# dual_encoder_i2c_shield_revA.net
KiCad netlist of a schematic drawn in EAGLE
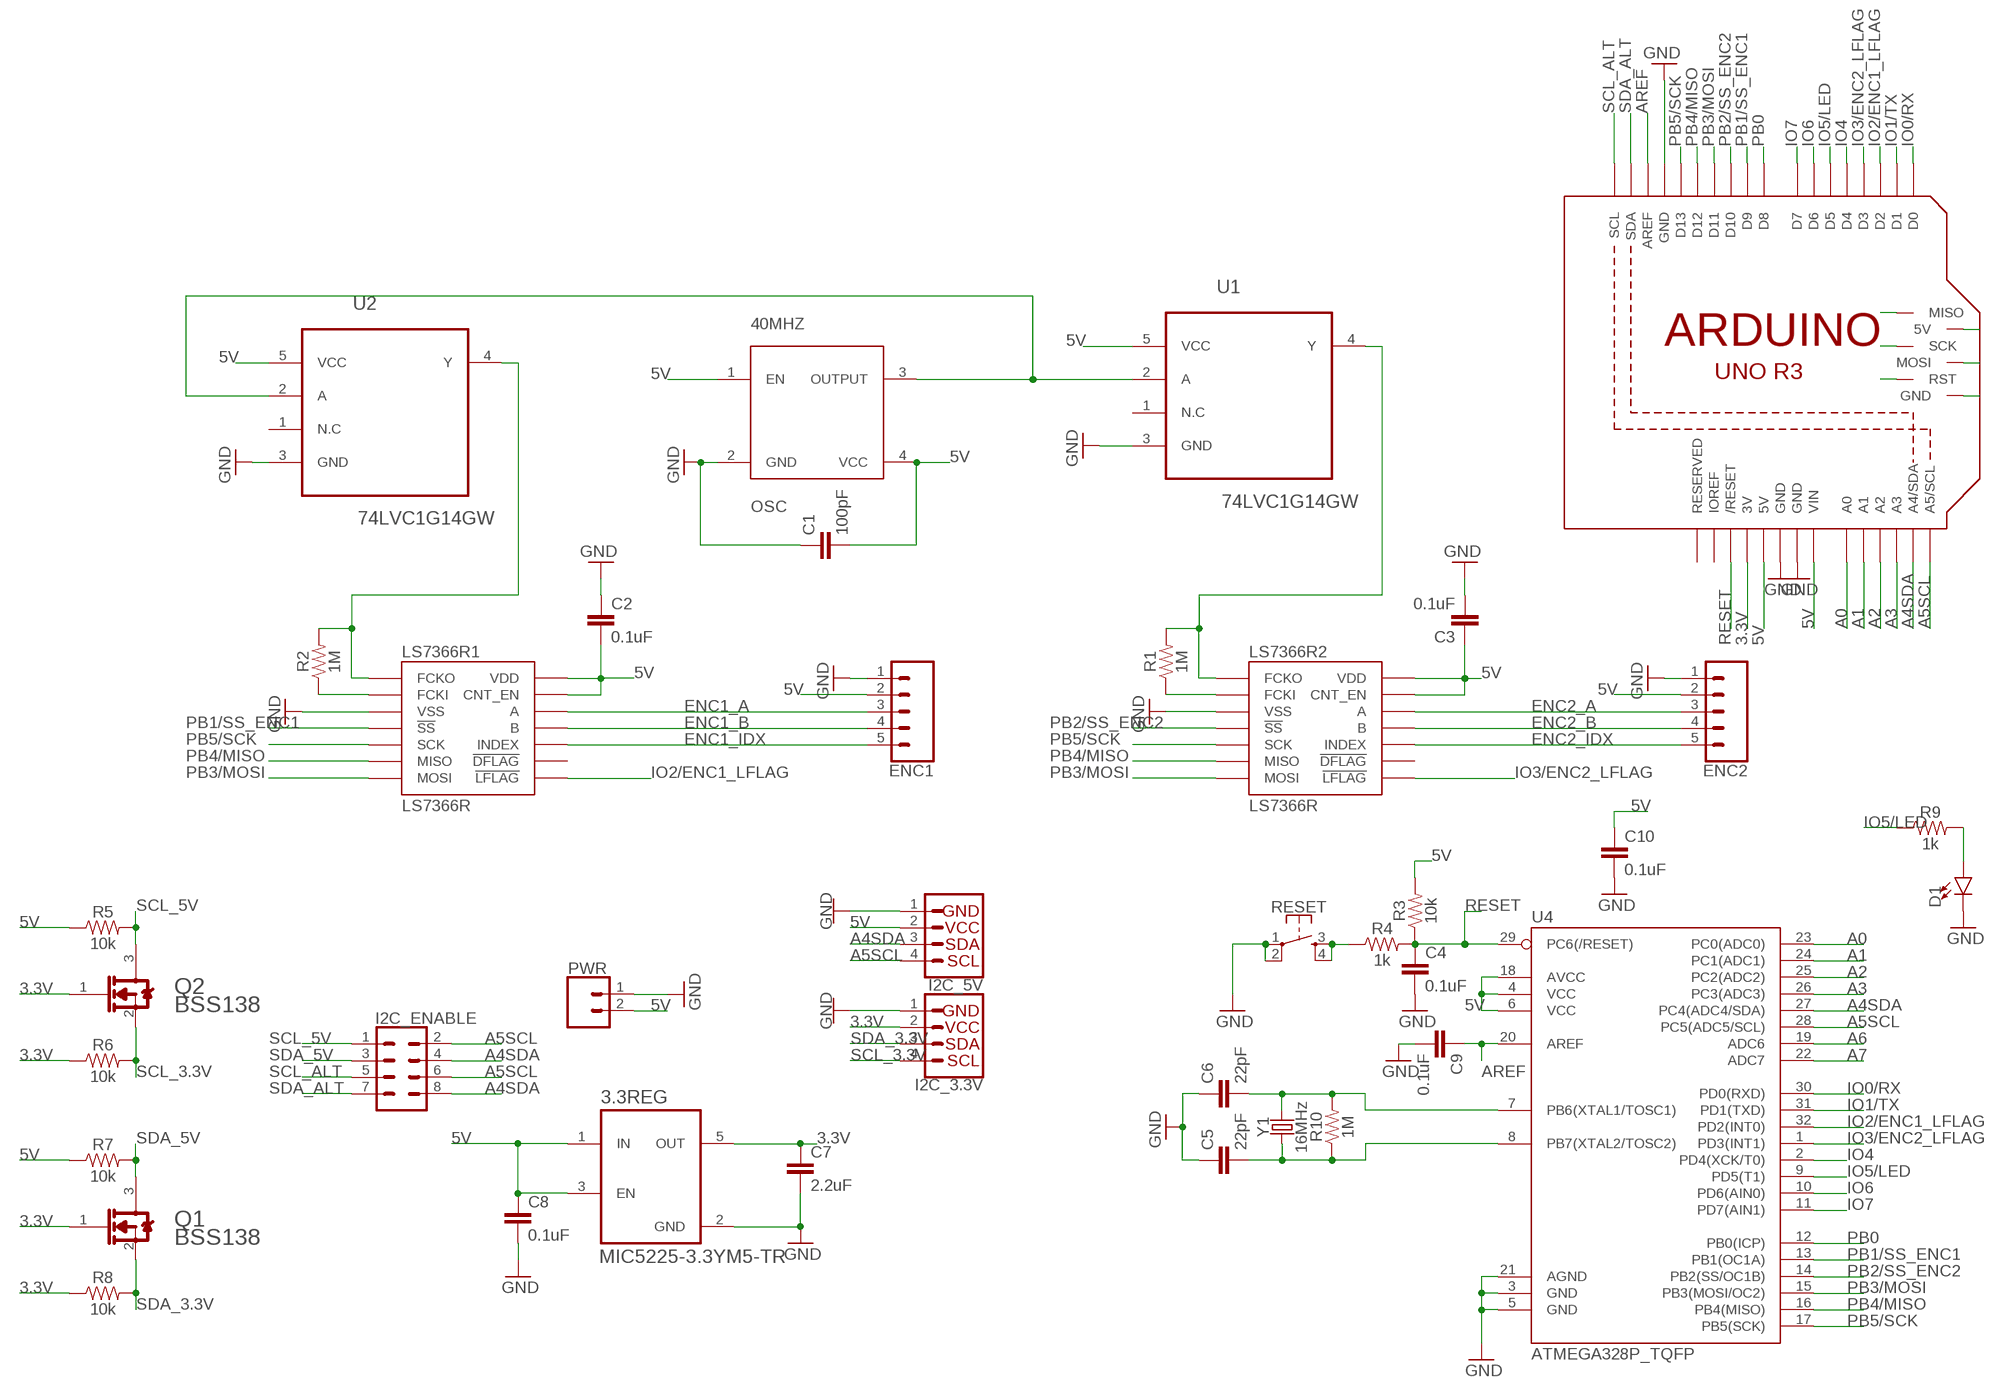
[diagram p0: schematic, sheet 1]

(export (version "E")
  (design (tool "Eeschema 10.0.6"))
  (components
    (comp (ref "3.3REG")
      (value "MIC5225-3.3YM5-TR")
      (footprint "eagle-import:SOT95P280X145-5N")
      (fields (field (name "MF") "Microchip"))
      (libsource (lib "eagle-import") (part "MIC5225-3.3YM5-TR"))
    )
    (comp (ref "40MHZ")
      (value "OSC")
      (footprint "eagle-import:CB3OSCILLATOR")
      (libsource (lib "eagle-import") (part "OSC"))
    )
    (comp (ref "C1")
      (value "100pF")
      (footprint "eagle-import:0603")
      (libsource (lib "eagle-import") (part "100PF-0603-50V-5%"))
    )
    (comp (ref "C2")
      (value "0.1uF")
      (footprint "eagle-import:0603")
      (libsource (lib "eagle-import") (part "0.1UF-0603-25V-5%"))
    )
    (comp (ref "C3")
      (value "0.1uF")
      (footprint "eagle-import:0603")
      (libsource (lib "eagle-import") (part "0.1UF-0603-25V-5%"))
    )
    (comp (ref "C4")
      (value "0.1uF")
      (footprint "eagle-import:0603")
      (libsource (lib "eagle-import") (part "0.1UF-0603-25V-5%"))
    )
    (comp (ref "C5")
      (value "22pF")
      (footprint "eagle-import:0603")
      (libsource (lib "eagle-import") (part "22PF-0603-50V-5%"))
    )
    (comp (ref "C6")
      (value "22pF")
      (footprint "eagle-import:0603")
      (libsource (lib "eagle-import") (part "22PF-0603-50V-5%"))
    )
    (comp (ref "C7")
      (value "2.2uF")
      (footprint "eagle-import:0603")
      (libsource (lib "eagle-import") (part "2.2UF-0603-10V-20%"))
    )
    (comp (ref "C8")
      (value "0.1uF")
      (footprint "eagle-import:0603")
      (libsource (lib "eagle-import") (part "0.1UF-0603-25V-5%"))
    )
    (comp (ref "C9")
      (value "0.1uF")
      (footprint "eagle-import:0603")
      (libsource (lib "eagle-import") (part "0.1UF-0603-25V-5%"))
    )
    (comp (ref "C10")
      (value "0.1uF")
      (footprint "eagle-import:0603")
      (libsource (lib "eagle-import") (part "0.1UF-0603-25V-5%"))
    )
    (comp (ref "D1")
      (value "LED0603")
      (footprint "eagle-import:LED-0603")
      (libsource (lib "eagle-import") (part "LED0603"))
    )
    (comp (ref "ENC1")
      (value "CONN_05")
      (footprint "eagle-import:1X05")
      (libsource (lib "eagle-import") (part "CONN_05"))
    )
    (comp (ref "ENC2")
      (value "CONN_05")
      (footprint "eagle-import:1X05")
      (libsource (lib "eagle-import") (part "CONN_05"))
    )
    (comp (ref "I2C_3.3V")
      (value "QWIIC_CONNECTORJS-1MM")
      (footprint "eagle-import:JST04_1MM_RA")
      (libsource (lib "eagle-import") (part "QWIIC_CONNECTORJS-1MM"))
    )
    (comp (ref "I2C_5V")
      (value "QWIIC_CONNECTORJS-1MM")
      (footprint "eagle-import:JST04_1MM_RA")
      (libsource (lib "eagle-import") (part "QWIIC_CONNECTORJS-1MM"))
    )
    (comp (ref "I2C_ENABLE")
      (value "CONN_04X2")
      (footprint "eagle-import:2X4")
      (libsource (lib "eagle-import") (part "CONN_04X2"))
    )
    (comp (ref "LS7366R1")
      (value "LS7366R")
      (footprint "eagle-import:SOIC14")
      (fields (field (name "MF") "LSI"))
      (libsource (lib "eagle-import") (part "LS7366R"))
    )
    (comp (ref "LS7366R2")
      (value "LS7366R")
      (footprint "eagle-import:SOIC14")
      (fields (field (name "MF") "LSI"))
      (libsource (lib "eagle-import") (part "LS7366R"))
    )
    (comp (ref "M1")
      (value "ARDUINO_R3_ICSP")
      (footprint "eagle-import:ARDUINOR3_ICSP")
      (libsource (lib "eagle-import") (part "ARDUINO_R3_ICSP"))
    )
    (comp (ref "PWR")
      (value "CONN_02-JST-2MM-SMT")
      (footprint "eagle-import:JST-2-SMD")
      (libsource (lib "eagle-import") (part "CONN_02-JST-2MM-SMT"))
    )
    (comp (ref "Q1")
      (value "ON_SEMI_BSS138ON_SEMI_BSS138_0_0")
      (footprint "eagle-import:ON_SEMI_BSS138_0")
      (fields
        (field (name "DIGIKEY_PART_NUMBER") "BSS138CT-ND")
        (field (name "MF") "ON Semi")
        (field (name "MOUSER_PART_NUMBER") "512-BSS138")
      )
      (libsource (lib "eagle-import") (part "ON_SEMI_BSS138ON_SEMI_BSS138_0_0"))
    )
    (comp (ref "Q2")
      (value "ON_SEMI_BSS138ON_SEMI_BSS138_0_0")
      (footprint "eagle-import:ON_SEMI_BSS138_0")
      (fields
        (field (name "DIGIKEY_PART_NUMBER") "BSS138CT-ND")
        (field (name "MF") "ON Semi")
        (field (name "MOUSER_PART_NUMBER") "512-BSS138")
      )
      (libsource (lib "eagle-import") (part "ON_SEMI_BSS138ON_SEMI_BSS138_0_0"))
    )
    (comp (ref "R1")
      (value "1M")
      (footprint "eagle-import:0603")
      (libsource (lib "eagle-import") (part "1MOHM-0603-1/4W-5%"))
    )
    (comp (ref "R2")
      (value "1M")
      (footprint "eagle-import:0603")
      (libsource (lib "eagle-import") (part "1MOHM-0603-1/4W-5%"))
    )
    (comp (ref "R3")
      (value "10k")
      (footprint "eagle-import:0603")
      (libsource (lib "eagle-import") (part "10KOHM-0603-1/10W-1%"))
    )
    (comp (ref "R4")
      (value "1k")
      (footprint "eagle-import:0603")
      (libsource (lib "eagle-import") (part "1KOHM-0603-1/10W-1%"))
    )
    (comp (ref "R5")
      (value "10k")
      (footprint "eagle-import:0603")
      (libsource (lib "eagle-import") (part "10KOHM-0603-1/10W-1%"))
    )
    (comp (ref "R6")
      (value "10k")
      (footprint "eagle-import:0603")
      (libsource (lib "eagle-import") (part "10KOHM-0603-1/10W-1%"))
    )
    (comp (ref "R7")
      (value "10k")
      (footprint "eagle-import:0603")
      (libsource (lib "eagle-import") (part "10KOHM-0603-1/10W-1%"))
    )
    (comp (ref "R8")
      (value "10k")
      (footprint "eagle-import:0603")
      (libsource (lib "eagle-import") (part "10KOHM-0603-1/10W-1%"))
    )
    (comp (ref "R9")
      (value "1k")
      (footprint "eagle-import:0603")
      (libsource (lib "eagle-import") (part "1KOHM-0603-1/10W-1%"))
    )
    (comp (ref "R10")
      (value "1M")
      (footprint "eagle-import:0603")
      (libsource (lib "eagle-import") (part "1MOHM-0603-1/4W-5%"))
    )
    (comp (ref "RESET")
      (value "MOMENTARY-SWITCH-SPST-2-SMD-5.2MM")
      (footprint "eagle-import:TACTILE_SWITCH_SMD_5.2MM")
      (libsource (lib "eagle-import") (part "MOMENTARY-SWITCH-SPST-2-SMD-5.2MM"))
    )
    (comp (ref "U1")
      (value "74LVC1G14GW")
      (footprint "eagle-import:SOT65P210X110-5N")
      (fields (field (name "MF") "NXP Semiconductors"))
      (libsource (lib "eagle-import") (part "74LVC1G14GW"))
    )
    (comp (ref "U2")
      (value "74LVC1G14GW")
      (footprint "eagle-import:SOT65P210X110-5N")
      (fields (field (name "MF") "NXP Semiconductors"))
      (libsource (lib "eagle-import") (part "74LVC1G14GW"))
    )
    (comp (ref "U4")
      (value "ATMEGA328P_TQFP")
      (footprint "eagle-import:TQFP32-08")
      (libsource (lib "eagle-import") (part "ATMEGA328P_TQFP"))
    )
    (comp (ref "Y1")
      (value "16MHz")
      (footprint "eagle-import:HC49US")
      (libsource (lib "eagle-import") (part "CRYSTAL-16MHZPTH-HC49US"))
    )
  )
  (nets
    (net (code "1") (name "/3.3V") (class "Default")
      (node (ref "3.3REG") (pin "5") (pinfunction "OUT_5") (pintype "output"))
      (node (ref "C7") (pin "1") (pinfunction "1_1") (pintype "passive"))
      (node (ref "I2C_3.3V") (pin "2") (pinfunction "2_2") (pintype "power_in"))
      (node (ref "M1") (pin "3V") (pinfunction "3V_3V") (pintype "power_in"))
      (node (ref "Q1") (pin "1") (pinfunction "G_1") (pintype "bidirectional"))
      (node (ref "Q2") (pin "1") (pinfunction "G_1") (pintype "bidirectional"))
      (node (ref "R6") (pin "1") (pinfunction "1_1") (pintype "passive"))
      (node (ref "R8") (pin "1") (pinfunction "1_1") (pintype "passive"))
    )
    (net (code "2") (name "/5V") (class "Default")
      (node (ref "3.3REG") (pin "1") (pinfunction "IN_1") (pintype "input"))
      (node (ref "3.3REG") (pin "3") (pinfunction "EN_3") (pintype "input"))
      (node (ref "40MHZ") (pin "1") (pinfunction "EN_1") (pintype "input"))
      (node (ref "40MHZ") (pin "4") (pinfunction "VCC_4") (pintype "input"))
      (node (ref "C1") (pin "2") (pinfunction "2_2") (pintype "passive"))
      (node (ref "C10") (pin "1") (pinfunction "1_1") (pintype "passive"))
      (node (ref "C2") (pin "2") (pinfunction "2_2") (pintype "passive"))
      (node (ref "C3") (pin "1") (pinfunction "1_1") (pintype "passive"))
      (node (ref "C8") (pin "1") (pinfunction "1_1") (pintype "passive"))
      (node (ref "ENC1") (pin "2") (pinfunction "2_2") (pintype "passive"))
      (node (ref "ENC2") (pin "2") (pinfunction "2_2") (pintype "passive"))
      (node (ref "I2C_5V") (pin "2") (pinfunction "2_2") (pintype "power_in"))
      (node (ref "LS7366R1") (pin "13") (pinfunction "CNT_EN_13") (pintype "bidirectional"))
      (node (ref "LS7366R1") (pin "14") (pinfunction "VDD_14") (pintype "bidirectional"))
      (node (ref "LS7366R2") (pin "13") (pinfunction "CNT_EN_13") (pintype "bidirectional"))
      (node (ref "LS7366R2") (pin "14") (pinfunction "VDD_14") (pintype "bidirectional"))
      (node (ref "M1") (pin "5V") (pinfunction "5V_5V") (pintype "power_in"))
      (node (ref "M1") (pin "5V_ICSP") (pinfunction "5V_5V_ICSP") (pintype "passive"))
      (node (ref "M1") (pin "VIN") (pinfunction "VIN_VIN") (pintype "power_in"))
      (node (ref "PWR") (pin "2") (pinfunction "1_2") (pintype "passive"))
      (node (ref "R3") (pin "2") (pinfunction "2_2") (pintype "passive"))
      (node (ref "R5") (pin "1") (pinfunction "1_1") (pintype "passive"))
      (node (ref "R7") (pin "1") (pinfunction "1_1") (pintype "passive"))
      (node (ref "U1") (pin "5") (pinfunction "VCC_5") (pintype "power_in"))
      (node (ref "U2") (pin "5") (pinfunction "VCC_5") (pintype "power_in"))
      (node (ref "U4") (pin "18") (pinfunction "AVCC_18") (pintype "bidirectional"))
      (node (ref "U4") (pin "4") (pinfunction "VCC_4") (pintype "bidirectional"))
      (node (ref "U4") (pin "6") (pinfunction "VCC_6") (pintype "bidirectional"))
    )
    (net (code "3") (name "/A0") (class "Default")
      (node (ref "M1") (pin "A0") (pinfunction "A0_A0") (pintype "bidirectional"))
      (node (ref "U4") (pin "23") (pinfunction "PC0(ADC0)_23") (pintype "bidirectional"))
    )
    (net (code "4") (name "/A1") (class "Default")
      (node (ref "M1") (pin "A1") (pinfunction "A1_A1") (pintype "bidirectional"))
      (node (ref "U4") (pin "24") (pinfunction "PC1(ADC1)_24") (pintype "bidirectional"))
    )
    (net (code "5") (name "/A2") (class "Default")
      (node (ref "M1") (pin "A2") (pinfunction "A2_A2") (pintype "bidirectional"))
      (node (ref "U4") (pin "25") (pinfunction "PC2(ADC2)_25") (pintype "bidirectional"))
    )
    (net (code "6") (name "/A3") (class "Default")
      (node (ref "M1") (pin "A3") (pinfunction "A3_A3") (pintype "bidirectional"))
      (node (ref "U4") (pin "26") (pinfunction "PC3(ADC3)_26") (pintype "bidirectional"))
    )
    (net (code "7") (name "/A4SDA") (class "Default")
      (node (ref "I2C_5V") (pin "3") (pinfunction "3_3") (pintype "passive"))
      (node (ref "I2C_ENABLE") (pin "4") (pinfunction "4_4") (pintype "passive"))
      (node (ref "I2C_ENABLE") (pin "8") (pinfunction "8_8") (pintype "passive"))
      (node (ref "M1") (pin "A4") (pinfunction "A4/SDA_A4") (pintype "bidirectional"))
      (node (ref "U4") (pin "27") (pinfunction "PC4(ADC4/SDA)_27") (pintype "bidirectional"))
    )
    (net (code "8") (name "/A5SCL") (class "Default")
      (node (ref "I2C_5V") (pin "4") (pinfunction "4_4") (pintype "passive"))
      (node (ref "I2C_ENABLE") (pin "2") (pinfunction "2_2") (pintype "passive"))
      (node (ref "I2C_ENABLE") (pin "6") (pinfunction "6_6") (pintype "passive"))
      (node (ref "M1") (pin "A5") (pinfunction "A5/SCL_A5") (pintype "bidirectional"))
      (node (ref "U4") (pin "28") (pinfunction "PC5(ADC5/SCL)_28") (pintype "bidirectional"))
    )
    (net (code "9") (name "/A6") (class "Default")
      (node (ref "U4") (pin "19") (pinfunction "ADC6_19") (pintype "bidirectional"))
    )
    (net (code "10") (name "/A7") (class "Default")
      (node (ref "U4") (pin "22") (pinfunction "ADC7_22") (pintype "bidirectional"))
    )
    (net (code "11") (name "/AREF") (class "Default")
      (node (ref "C9") (pin "1") (pinfunction "1_1") (pintype "passive"))
      (node (ref "M1") (pin "AREF") (pinfunction "AREF_AREF") (pintype "bidirectional"))
      (node (ref "U4") (pin "20") (pinfunction "AREF_20") (pintype "bidirectional"))
    )
    (net (code "12") (name "/ENC1_A") (class "Default")
      (node (ref "ENC1") (pin "3") (pinfunction "3_3") (pintype "passive"))
      (node (ref "LS7366R1") (pin "12") (pinfunction "A_12") (pintype "bidirectional"))
    )
    (net (code "13") (name "/ENC1_B") (class "Default")
      (node (ref "ENC1") (pin "4") (pinfunction "4_4") (pintype "passive"))
      (node (ref "LS7366R1") (pin "11") (pinfunction "B_11") (pintype "bidirectional"))
    )
    (net (code "14") (name "/ENC1_IDX") (class "Default")
      (node (ref "ENC1") (pin "5") (pinfunction "5_5") (pintype "passive"))
      (node (ref "LS7366R1") (pin "10") (pinfunction "INDEX_10") (pintype "bidirectional"))
    )
    (net (code "15") (name "/ENC2_A") (class "Default")
      (node (ref "ENC2") (pin "3") (pinfunction "3_3") (pintype "passive"))
      (node (ref "LS7366R2") (pin "12") (pinfunction "A_12") (pintype "bidirectional"))
    )
    (net (code "16") (name "/ENC2_B") (class "Default")
      (node (ref "ENC2") (pin "4") (pinfunction "4_4") (pintype "passive"))
      (node (ref "LS7366R2") (pin "11") (pinfunction "B_11") (pintype "bidirectional"))
    )
    (net (code "17") (name "/ENC2_IDX") (class "Default")
      (node (ref "ENC2") (pin "5") (pinfunction "5_5") (pintype "passive"))
      (node (ref "LS7366R2") (pin "10") (pinfunction "INDEX_10") (pintype "bidirectional"))
    )
    (net (code "18") (name "/IO0{slash}RX") (class "Default")
      (node (ref "M1") (pin "D0") (pinfunction "D0_D0") (pintype "bidirectional"))
      (node (ref "U4") (pin "30") (pinfunction "PD0(RXD)_30") (pintype "bidirectional"))
    )
    (net (code "19") (name "/IO1{slash}TX") (class "Default")
      (node (ref "M1") (pin "D1") (pinfunction "D1_D1") (pintype "bidirectional"))
      (node (ref "U4") (pin "31") (pinfunction "PD1(TXD)_31") (pintype "bidirectional"))
    )
    (net (code "20") (name "/IO2{slash}ENC1_LFLAG") (class "Default")
      (node (ref "LS7366R1") (pin "8") (pinfunction "~{LFLAG}_8") (pintype "bidirectional"))
      (node (ref "M1") (pin "D2") (pinfunction "D2_D2") (pintype "bidirectional"))
      (node (ref "U4") (pin "32") (pinfunction "PD2(INT0)_32") (pintype "bidirectional"))
    )
    (net (code "21") (name "/IO3{slash}ENC2_LFLAG") (class "Default")
      (node (ref "LS7366R2") (pin "8") (pinfunction "~{LFLAG}_8") (pintype "bidirectional"))
      (node (ref "M1") (pin "D3") (pinfunction "D3_D3") (pintype "bidirectional"))
      (node (ref "U4") (pin "1") (pinfunction "PD3(INT1)_1") (pintype "bidirectional"))
    )
    (net (code "22") (name "/IO4") (class "Default")
      (node (ref "M1") (pin "D4") (pinfunction "D4_D4") (pintype "bidirectional"))
      (node (ref "U4") (pin "2") (pinfunction "PD4(XCK/T0)_2") (pintype "bidirectional"))
    )
    (net (code "23") (name "/IO5{slash}LED") (class "Default")
      (node (ref "M1") (pin "D5") (pinfunction "D5_D5") (pintype "bidirectional"))
      (node (ref "R9") (pin "1") (pinfunction "1_1") (pintype "passive"))
      (node (ref "U4") (pin "9") (pinfunction "PD5(T1)_9") (pintype "bidirectional"))
    )
    (net (code "24") (name "/IO6") (class "Default")
      (node (ref "M1") (pin "D6") (pinfunction "D6_D6") (pintype "bidirectional"))
      (node (ref "U4") (pin "10") (pinfunction "PD6(AIN0)_10") (pintype "bidirectional"))
    )
    (net (code "25") (name "/IO7") (class "Default")
      (node (ref "M1") (pin "D7") (pinfunction "D7_D7") (pintype "bidirectional"))
      (node (ref "U4") (pin "11") (pinfunction "PD7(AIN1)_11") (pintype "bidirectional"))
    )
    (net (code "26") (name "/PB0") (class "Default")
      (node (ref "M1") (pin "D8") (pinfunction "D8_D8") (pintype "bidirectional"))
      (node (ref "U4") (pin "12") (pinfunction "PB0(ICP)_12") (pintype "bidirectional"))
    )
    (net (code "27") (name "/PB1{slash}SS_ENC1") (class "Default")
      (node (ref "LS7366R1") (pin "4") (pinfunction "~{SS}_4") (pintype "bidirectional"))
      (node (ref "M1") (pin "D9") (pinfunction "D9_D9") (pintype "bidirectional"))
      (node (ref "U4") (pin "13") (pinfunction "PB1(OC1A)_13") (pintype "bidirectional"))
    )
    (net (code "28") (name "/PB2{slash}SS_ENC2") (class "Default")
      (node (ref "LS7366R2") (pin "4") (pinfunction "~{SS}_4") (pintype "bidirectional"))
      (node (ref "M1") (pin "D10") (pinfunction "D10_D10") (pintype "bidirectional"))
      (node (ref "U4") (pin "14") (pinfunction "PB2(SS/OC1B)_14") (pintype "bidirectional"))
    )
    (net (code "29") (name "/PB3{slash}MOSI") (class "Default")
      (node (ref "LS7366R1") (pin "7") (pinfunction "MOSI_7") (pintype "bidirectional"))
      (node (ref "LS7366R2") (pin "7") (pinfunction "MOSI_7") (pintype "bidirectional"))
      (node (ref "M1") (pin "D11") (pinfunction "D11_D11") (pintype "bidirectional"))
      (node (ref "M1") (pin "MOSI") (pinfunction "MOSI_MOSI") (pintype "passive"))
      (node (ref "U4") (pin "15") (pinfunction "PB3(MOSI/OC2)_15") (pintype "bidirectional"))
    )
    (net (code "30") (name "/PB4{slash}MISO") (class "Default")
      (node (ref "LS7366R1") (pin "6") (pinfunction "MISO_6") (pintype "bidirectional"))
      (node (ref "LS7366R2") (pin "6") (pinfunction "MISO_6") (pintype "bidirectional"))
      (node (ref "M1") (pin "D12") (pinfunction "D12_D12") (pintype "bidirectional"))
      (node (ref "M1") (pin "MISO") (pinfunction "MISO_MISO") (pintype "passive"))
      (node (ref "U4") (pin "16") (pinfunction "PB4(MISO)_16") (pintype "bidirectional"))
    )
    (net (code "31") (name "/PB5{slash}SCK") (class "Default")
      (node (ref "LS7366R1") (pin "5") (pinfunction "SCK_5") (pintype "bidirectional"))
      (node (ref "LS7366R2") (pin "5") (pinfunction "SCK_5") (pintype "bidirectional"))
      (node (ref "M1") (pin "D13") (pinfunction "D13_D13") (pintype "bidirectional"))
      (node (ref "M1") (pin "SCK") (pinfunction "SCK_SCK") (pintype "passive"))
      (node (ref "U4") (pin "17") (pinfunction "PB5(SCK)_17") (pintype "bidirectional"))
    )
    (net (code "32") (name "/RESET") (class "Default")
      (node (ref "C4") (pin "1") (pinfunction "1_1") (pintype "passive"))
      (node (ref "M1") (pin "RESET") (pinfunction "/RESET_RESET") (pintype "bidirectional"))
      (node (ref "M1") (pin "RESET_ICSP") (pinfunction "RST_RESET_ICSP") (pintype "passive"))
      (node (ref "R3") (pin "1") (pinfunction "1_1") (pintype "passive"))
      (node (ref "R4") (pin "2") (pinfunction "2_2") (pintype "passive"))
      (node (ref "U4") (pin "29") (pinfunction "PC6(/RESET)_29") (pintype "bidirectional"))
    )
    (net (code "33") (name "/SCL_3.3V") (class "Default")
      (node (ref "I2C_3.3V") (pin "4") (pinfunction "4_4") (pintype "passive"))
      (node (ref "Q2") (pin "2") (pinfunction "S_2") (pintype "bidirectional"))
      (node (ref "R6") (pin "2") (pinfunction "2_2") (pintype "passive"))
    )
    (net (code "34") (name "/SCL_5V") (class "Default")
      (node (ref "I2C_ENABLE") (pin "1") (pinfunction "1_1") (pintype "passive"))
      (node (ref "Q2") (pin "3") (pinfunction "D_3") (pintype "bidirectional"))
      (node (ref "R5") (pin "2") (pinfunction "2_2") (pintype "passive"))
    )
    (net (code "35") (name "/SCL_ALT") (class "Default")
      (node (ref "I2C_ENABLE") (pin "5") (pinfunction "5_5") (pintype "passive"))
      (node (ref "M1") (pin "SCL") (pinfunction "SCL_SCL") (pintype "bidirectional"))
    )
    (net (code "36") (name "/SDA_3.3V") (class "Default")
      (node (ref "I2C_3.3V") (pin "3") (pinfunction "3_3") (pintype "passive"))
      (node (ref "Q1") (pin "2") (pinfunction "S_2") (pintype "bidirectional"))
      (node (ref "R8") (pin "2") (pinfunction "2_2") (pintype "passive"))
    )
    (net (code "37") (name "/SDA_5V") (class "Default")
      (node (ref "I2C_ENABLE") (pin "3") (pinfunction "3_3") (pintype "passive"))
      (node (ref "Q1") (pin "3") (pinfunction "D_3") (pintype "bidirectional"))
      (node (ref "R7") (pin "2") (pinfunction "2_2") (pintype "passive"))
    )
    (net (code "38") (name "/SDA_ALT") (class "Default")
      (node (ref "I2C_ENABLE") (pin "7") (pinfunction "7_7") (pintype "passive"))
      (node (ref "M1") (pin "SDA") (pinfunction "SDA_SDA") (pintype "bidirectional"))
    )
    (net (code "39") (name "GND") (class "Default")
      (node (ref "3.3REG") (pin "2") (pinfunction "GND_2") (pintype "power_in"))
      (node (ref "40MHZ") (pin "2") (pinfunction "GND_2") (pintype "input"))
      (node (ref "C1") (pin "1") (pinfunction "1_1") (pintype "passive"))
      (node (ref "C10") (pin "2") (pinfunction "2_2") (pintype "passive"))
      (node (ref "C2") (pin "1") (pinfunction "1_1") (pintype "passive"))
      (node (ref "C3") (pin "2") (pinfunction "2_2") (pintype "passive"))
      (node (ref "C4") (pin "2") (pinfunction "2_2") (pintype "passive"))
      (node (ref "C5") (pin "1") (pinfunction "1_1") (pintype "passive"))
      (node (ref "C6") (pin "1") (pinfunction "1_1") (pintype "passive"))
      (node (ref "C7") (pin "2") (pinfunction "2_2") (pintype "passive"))
      (node (ref "C8") (pin "2") (pinfunction "2_2") (pintype "passive"))
      (node (ref "C9") (pin "2") (pinfunction "2_2") (pintype "passive"))
      (node (ref "D1") (pin "C") (pinfunction "C_C") (pintype "passive"))
      (node (ref "ENC1") (pin "1") (pinfunction "1_1") (pintype "passive"))
      (node (ref "ENC2") (pin "1") (pinfunction "1_1") (pintype "passive"))
      (node (ref "I2C_3.3V") (pin "1") (pinfunction "1_1") (pintype "power_in"))
      (node (ref "I2C_5V") (pin "1") (pinfunction "1_1") (pintype "power_in"))
      (node (ref "LS7366R1") (pin "3") (pinfunction "VSS_3") (pintype "bidirectional"))
      (node (ref "LS7366R2") (pin "3") (pinfunction "VSS_3") (pintype "bidirectional"))
      (node (ref "M1") (pin "GND") (pinfunction "GND_GND") (pintype "power_in"))
      (node (ref "M1") (pin "GND@1") (pinfunction "GND_GND@1") (pintype "power_in"))
      (node (ref "M1") (pin "GND@2") (pinfunction "GND_GND@2") (pintype "passive"))
      (node (ref "M1") (pin "GND@3") (pinfunction "GND_GND@3") (pintype "power_in"))
      (node (ref "PWR") (pin "1") (pinfunction "2_1") (pintype "passive"))
      (node (ref "RESET") (pin "1") (pinfunction "1_1") (pintype "passive"))
      (node (ref "RESET") (pin "2") (pinfunction "2_2") (pintype "passive"))
      (node (ref "U1") (pin "3") (pinfunction "GND_3") (pintype "passive"))
      (node (ref "U2") (pin "3") (pinfunction "GND_3") (pintype "passive"))
      (node (ref "U4") (pin "21") (pinfunction "AGND_21") (pintype "bidirectional"))
      (node (ref "U4") (pin "3") (pinfunction "GND_3") (pintype "bidirectional"))
      (node (ref "U4") (pin "5") (pinfunction "GND_5") (pintype "bidirectional"))
    )
    (net (code "40") (name "Net-(40MHZ-OUTPUT)") (class "Default")
      (node (ref "40MHZ") (pin "3") (pinfunction "OUTPUT_3") (pintype "output"))
      (node (ref "U1") (pin "2") (pinfunction "A_2") (pintype "input"))
      (node (ref "U2") (pin "2") (pinfunction "A_2") (pintype "input"))
    )
    (net (code "41") (name "Net-(D1-PadA)") (class "Default")
      (node (ref "D1") (pin "A") (pinfunction "A_A") (pintype "passive"))
      (node (ref "R9") (pin "2") (pinfunction "2_2") (pintype "passive"))
    )
    (net (code "42") (name "Net-(LS7366R1-FCKI)") (class "Default")
      (node (ref "LS7366R1") (pin "2") (pinfunction "FCKI_2") (pintype "bidirectional"))
      (node (ref "R2") (pin "1") (pinfunction "1_1") (pintype "passive"))
    )
    (net (code "43") (name "Net-(LS7366R1-FCKO)") (class "Default")
      (node (ref "LS7366R1") (pin "1") (pinfunction "FCKO_1") (pintype "bidirectional"))
      (node (ref "R2") (pin "2") (pinfunction "2_2") (pintype "passive"))
      (node (ref "U2") (pin "4") (pinfunction "Y_4") (pintype "output"))
    )
    (net (code "44") (name "Net-(LS7366R2-FCKI)") (class "Default")
      (node (ref "LS7366R2") (pin "2") (pinfunction "FCKI_2") (pintype "bidirectional"))
      (node (ref "R1") (pin "1") (pinfunction "1_1") (pintype "passive"))
    )
    (net (code "45") (name "Net-(LS7366R2-FCKO)") (class "Default")
      (node (ref "LS7366R2") (pin "1") (pinfunction "FCKO_1") (pintype "bidirectional"))
      (node (ref "R1") (pin "2") (pinfunction "2_2") (pintype "passive"))
      (node (ref "U1") (pin "4") (pinfunction "Y_4") (pintype "output"))
    )
    (net (code "46") (name "Net-(R4-Pad1)") (class "Default")
      (node (ref "R4") (pin "1") (pinfunction "1_1") (pintype "passive"))
      (node (ref "RESET") (pin "3") (pinfunction "3_3") (pintype "passive"))
      (node (ref "RESET") (pin "4") (pinfunction "4_4") (pintype "passive"))
    )
    (net (code "47") (name "Net-(U4-PB6(XTAL1{slash}TOSC1))") (class "Default")
      (node (ref "C6") (pin "2") (pinfunction "2_2") (pintype "passive"))
      (node (ref "R10") (pin "2") (pinfunction "2_2") (pintype "passive"))
      (node (ref "U4") (pin "7") (pinfunction "PB6(XTAL1/TOSC1)_7") (pintype "bidirectional"))
      (node (ref "Y1") (pin "2") (pinfunction "2_2") (pintype "passive"))
    )
    (net (code "48") (name "Net-(U4-PB7(XTAL2{slash}TOSC2))") (class "Default")
      (node (ref "C5") (pin "2") (pinfunction "2_2") (pintype "passive"))
      (node (ref "R10") (pin "1") (pinfunction "1_1") (pintype "passive"))
      (node (ref "U4") (pin "8") (pinfunction "PB7(XTAL2/TOSC2)_8") (pintype "bidirectional"))
      (node (ref "Y1") (pin "1") (pinfunction "1_1") (pintype "passive"))
    )
    (net (code "49") (name "unconnected-(LS7366R1-~{DFLAG}-Pad9)") (class "Default")
      (node (ref "LS7366R1") (pin "9") (pinfunction "~{DFLAG}_9") (pintype "bidirectional"))
    )
    (net (code "50") (name "unconnected-(LS7366R2-~{DFLAG}-Pad9)") (class "Default")
      (node (ref "LS7366R2") (pin "9") (pinfunction "~{DFLAG}_9") (pintype "bidirectional"))
    )
    (net (code "51") (name "unconnected-(M1-PadIOREF)") (class "Default")
      (node (ref "M1") (pin "IOREF") (pinfunction "IOREF_IOREF") (pintype "output"))
    )
    (net (code "52") (name "unconnected-(M1-PadRESERVED)") (class "Default")
      (node (ref "M1") (pin "RESERVED") (pinfunction "RESERVED_RESERVED") (pintype "no_connect"))
    )
    (net (code "53") (name "unconnected-(U1-N.C-Pad1)") (class "Default")
      (node (ref "U1") (pin "1") (pinfunction "N.C_1") (pintype "no_connect"))
    )
    (net (code "54") (name "unconnected-(U2-N.C-Pad1)") (class "Default")
      (node (ref "U2") (pin "1") (pinfunction "N.C_1") (pintype "no_connect"))
    )
  )
)
